# working.net
KiCad netlist of a schematic drawn in EAGLE
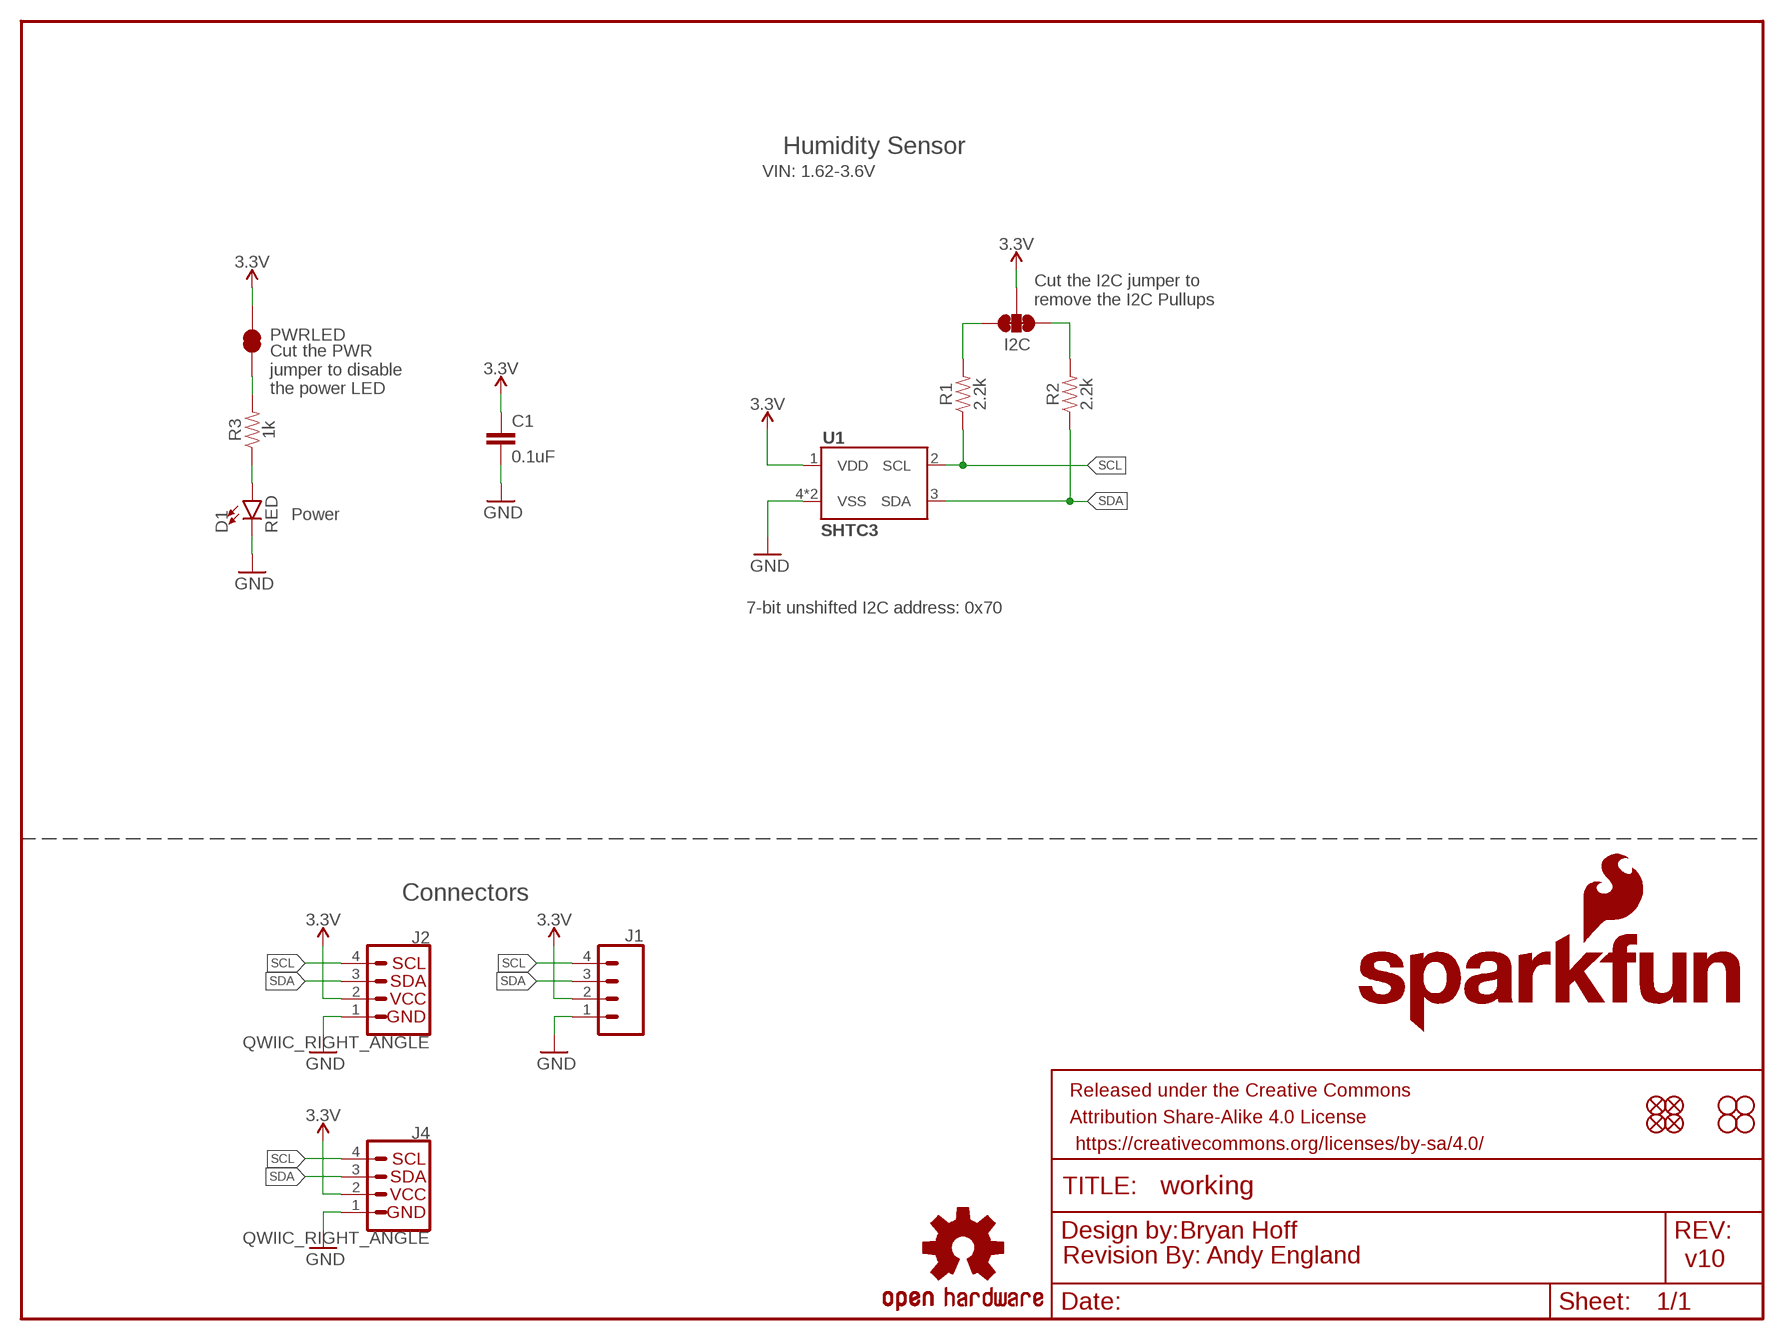
[diagram p0: schematic, sheet 1]

(export (version "E")
  (design (tool "Eeschema 10.0.6"))
  (components
    (comp (ref "C1")
      (value "0.1uF")
      (footprint "eagle-import:0603")
      (libsource (lib "eagle-import") (part "0.1UF-0603-25V-(+80/-20%)"))
    )
    (comp (ref "D1")
      (value "RED")
      (footprint "eagle-import:LED-0603")
      (libsource (lib "eagle-import") (part "LED-RED0603"))
    )
    (comp (ref "FRAME1")
      (value "FRAME-LETTER")
      (footprint "eagle-import:CREATIVE_COMMONS")
      (libsource (lib "eagle-import") (part "FRAME-LETTER"))
    )
    (comp (ref "I2C")
      (value "JUMPER-SMT_3_2-NC_TRACE_SILK")
      (footprint "eagle-import:SMT-JUMPER_3_2-NC_TRACE_SILK")
      (libsource (lib "eagle-import") (part "JUMPER-SMT_3_2-NC_TRACE_SILK"))
    )
    (comp (ref "J1")
      (value "CONN_041X04_NO_SILK")
      (footprint "eagle-import:1X04_NO_SILK")
      (libsource (lib "eagle-import") (part "CONN_041X04_NO_SILK"))
    )
    (comp (ref "J2")
      (value "QWIIC_RIGHT_ANGLE")
      (footprint "eagle-import:JST04_1MM_RA")
      (libsource (lib "eagle-import") (part "QWIIC_CONNECTORJS-1MM"))
    )
    (comp (ref "J4")
      (value "QWIIC_RIGHT_ANGLE")
      (footprint "eagle-import:JST04_1MM_RA")
      (libsource (lib "eagle-import") (part "QWIIC_CONNECTORJS-1MM"))
    )
    (comp (ref "JP1")
      (value "FIDUCIALUFIDUCIAL")
      (footprint "eagle-import:MICRO-FIDUCIAL")
      (libsource (lib "eagle-import") (part "FIDUCIALUFIDUCIAL"))
    )
    (comp (ref "JP2")
      (value "FIDUCIALUFIDUCIAL")
      (footprint "eagle-import:MICRO-FIDUCIAL")
      (libsource (lib "eagle-import") (part "FIDUCIALUFIDUCIAL"))
    )
    (comp (ref "JP3")
      (value "STAND-OFF")
      (footprint "eagle-import:STAND-OFF")
      (libsource (lib "eagle-import") (part "STAND-OFF"))
    )
    (comp (ref "JP4")
      (value "STAND-OFF")
      (footprint "eagle-import:STAND-OFF")
      (libsource (lib "eagle-import") (part "STAND-OFF"))
    )
    (comp (ref "JP5")
      (value "FIDUCIALUFIDUCIAL")
      (footprint "eagle-import:MICRO-FIDUCIAL")
      (libsource (lib "eagle-import") (part "FIDUCIALUFIDUCIAL"))
    )
    (comp (ref "JP6")
      (value "FIDUCIALUFIDUCIAL")
      (footprint "eagle-import:MICRO-FIDUCIAL")
      (libsource (lib "eagle-import") (part "FIDUCIALUFIDUCIAL"))
    )
    (comp (ref "JP7")
      (value "STAND-OFF")
      (footprint "eagle-import:STAND-OFF")
      (libsource (lib "eagle-import") (part "STAND-OFF"))
    )
    (comp (ref "JP8")
      (value "STAND-OFF")
      (footprint "eagle-import:STAND-OFF")
      (libsource (lib "eagle-import") (part "STAND-OFF"))
    )
    (comp (ref "LOGO1")
      (value "OSHW-LOGOMINI")
      (footprint "eagle-import:OSHW-LOGO-MINI")
      (libsource (lib "eagle-import") (part "OSHW-LOGOMINI"))
    )
    (comp (ref "LOGO2")
      (value "SFE_LOGO_NAME_FLAME.1_INCH")
      (footprint "eagle-import:SFE_LOGO_NAME_FLAME_.1")
      (libsource (lib "eagle-import") (part "SFE_LOGO_NAME_FLAME.1_INCH"))
    )
    (comp (ref "LOGO3")
      (value "SFE_LOGO_NAME_FLAME.1_INCH")
      (footprint "eagle-import:SFE_LOGO_NAME_FLAME_.1")
      (libsource (lib "eagle-import") (part "SFE_LOGO_NAME_FLAME.1_INCH"))
    )
    (comp (ref "LOGO4")
      (value "REVISION")
      (footprint "eagle-import:REVISION")
      (libsource (lib "eagle-import") (part "REVISION"))
    )
    (comp (ref "PWRLED")
      (value "JUMPER-SMT_2_NC_TRACE_SILK")
      (footprint "eagle-import:SMT-JUMPER_2_NC_TRACE_SILK")
      (libsource (lib "eagle-import") (part "JUMPER-SMT_2_NC_TRACE_SILK"))
    )
    (comp (ref "R1")
      (value "2.2k")
      (footprint "eagle-import:0603")
      (libsource (lib "eagle-import") (part "2.2KOHM-0603-1/10W-1%"))
    )
    (comp (ref "R2")
      (value "2.2k")
      (footprint "eagle-import:0603")
      (libsource (lib "eagle-import") (part "2.2KOHM-0603-1/10W-1%"))
    )
    (comp (ref "R3")
      (value "1k")
      (footprint "eagle-import:0603")
      (libsource (lib "eagle-import") (part "1KOHM-0603-1/10W-1%"))
    )
    (comp (ref "U1")
      (value "SHTC3")
      (footprint "eagle-import:SHTC3")
      (libsource (lib "eagle-import") (part "SHTC3"))
    )
  )
  (nets
    (net (code "1") (name "3.3V") (class "Default")
      (node (ref "C1") (pin "1") (pinfunction "1_1") (pintype "passive"))
      (node (ref "I2C") (pin "2") (pinfunction "2_2") (pintype "passive"))
      (node (ref "J1") (pin "2") (pinfunction "2_2") (pintype "passive"))
      (node (ref "J2") (pin "2") (pinfunction "2_2") (pintype "power_in"))
      (node (ref "J4") (pin "2") (pinfunction "2_2") (pintype "power_in"))
      (node (ref "PWRLED") (pin "2") (pinfunction "2_2") (pintype "passive"))
      (node (ref "U1") (pin "1") (pinfunction "VDD_1") (pintype "bidirectional"))
    )
    (net (code "2") (name "GND") (class "Default")
      (node (ref "C1") (pin "2") (pinfunction "2_2") (pintype "passive"))
      (node (ref "D1") (pin "C") (pinfunction "C_C") (pintype "passive"))
      (node (ref "J1") (pin "1") (pinfunction "1_1") (pintype "passive"))
      (node (ref "J2") (pin "1") (pinfunction "1_1") (pintype "power_in"))
      (node (ref "J4") (pin "1") (pinfunction "1_1") (pintype "power_in"))
      (node (ref "U1") (pin "4") (pinfunction "VSS_4") (pintype "bidirectional"))
      (node (ref "U1") (pin "5") (pinfunction "VSS_5") (pintype "bidirectional"))
    )
    (net (code "3") (name "Net-(D1-PadA)") (class "Default")
      (node (ref "D1") (pin "A") (pinfunction "A_A") (pintype "passive"))
      (node (ref "R3") (pin "1") (pinfunction "1_1") (pintype "passive"))
    )
    (net (code "4") (name "Net-(I2C-Pad1)") (class "Default")
      (node (ref "I2C") (pin "1") (pinfunction "1_1") (pintype "passive"))
      (node (ref "R2") (pin "2") (pinfunction "2_2") (pintype "passive"))
    )
    (net (code "5") (name "Net-(I2C-Pad3)") (class "Default")
      (node (ref "I2C") (pin "3") (pinfunction "3_3") (pintype "passive"))
      (node (ref "R1") (pin "2") (pinfunction "2_2") (pintype "passive"))
    )
    (net (code "6") (name "Net-(PWRLED-Pad1)") (class "Default")
      (node (ref "PWRLED") (pin "1") (pinfunction "1_1") (pintype "passive"))
      (node (ref "R3") (pin "2") (pinfunction "2_2") (pintype "passive"))
    )
    (net (code "7") (name "SCL") (class "Default")
      (node (ref "J1") (pin "4") (pinfunction "4_4") (pintype "passive"))
      (node (ref "J2") (pin "4") (pinfunction "4_4") (pintype "passive"))
      (node (ref "J4") (pin "4") (pinfunction "4_4") (pintype "passive"))
      (node (ref "R1") (pin "1") (pinfunction "1_1") (pintype "passive"))
      (node (ref "U1") (pin "2") (pinfunction "SCL_2") (pintype "bidirectional"))
    )
    (net (code "8") (name "SDA") (class "Default")
      (node (ref "J1") (pin "3") (pinfunction "3_3") (pintype "passive"))
      (node (ref "J2") (pin "3") (pinfunction "3_3") (pintype "passive"))
      (node (ref "J4") (pin "3") (pinfunction "3_3") (pintype "passive"))
      (node (ref "R2") (pin "1") (pinfunction "1_1") (pintype "passive"))
      (node (ref "U1") (pin "3") (pinfunction "SDA_3") (pintype "bidirectional"))
    )
  )
)
